# 08_-_Resolver.net
KiCad netlist of a schematic drawn in Altium Designer
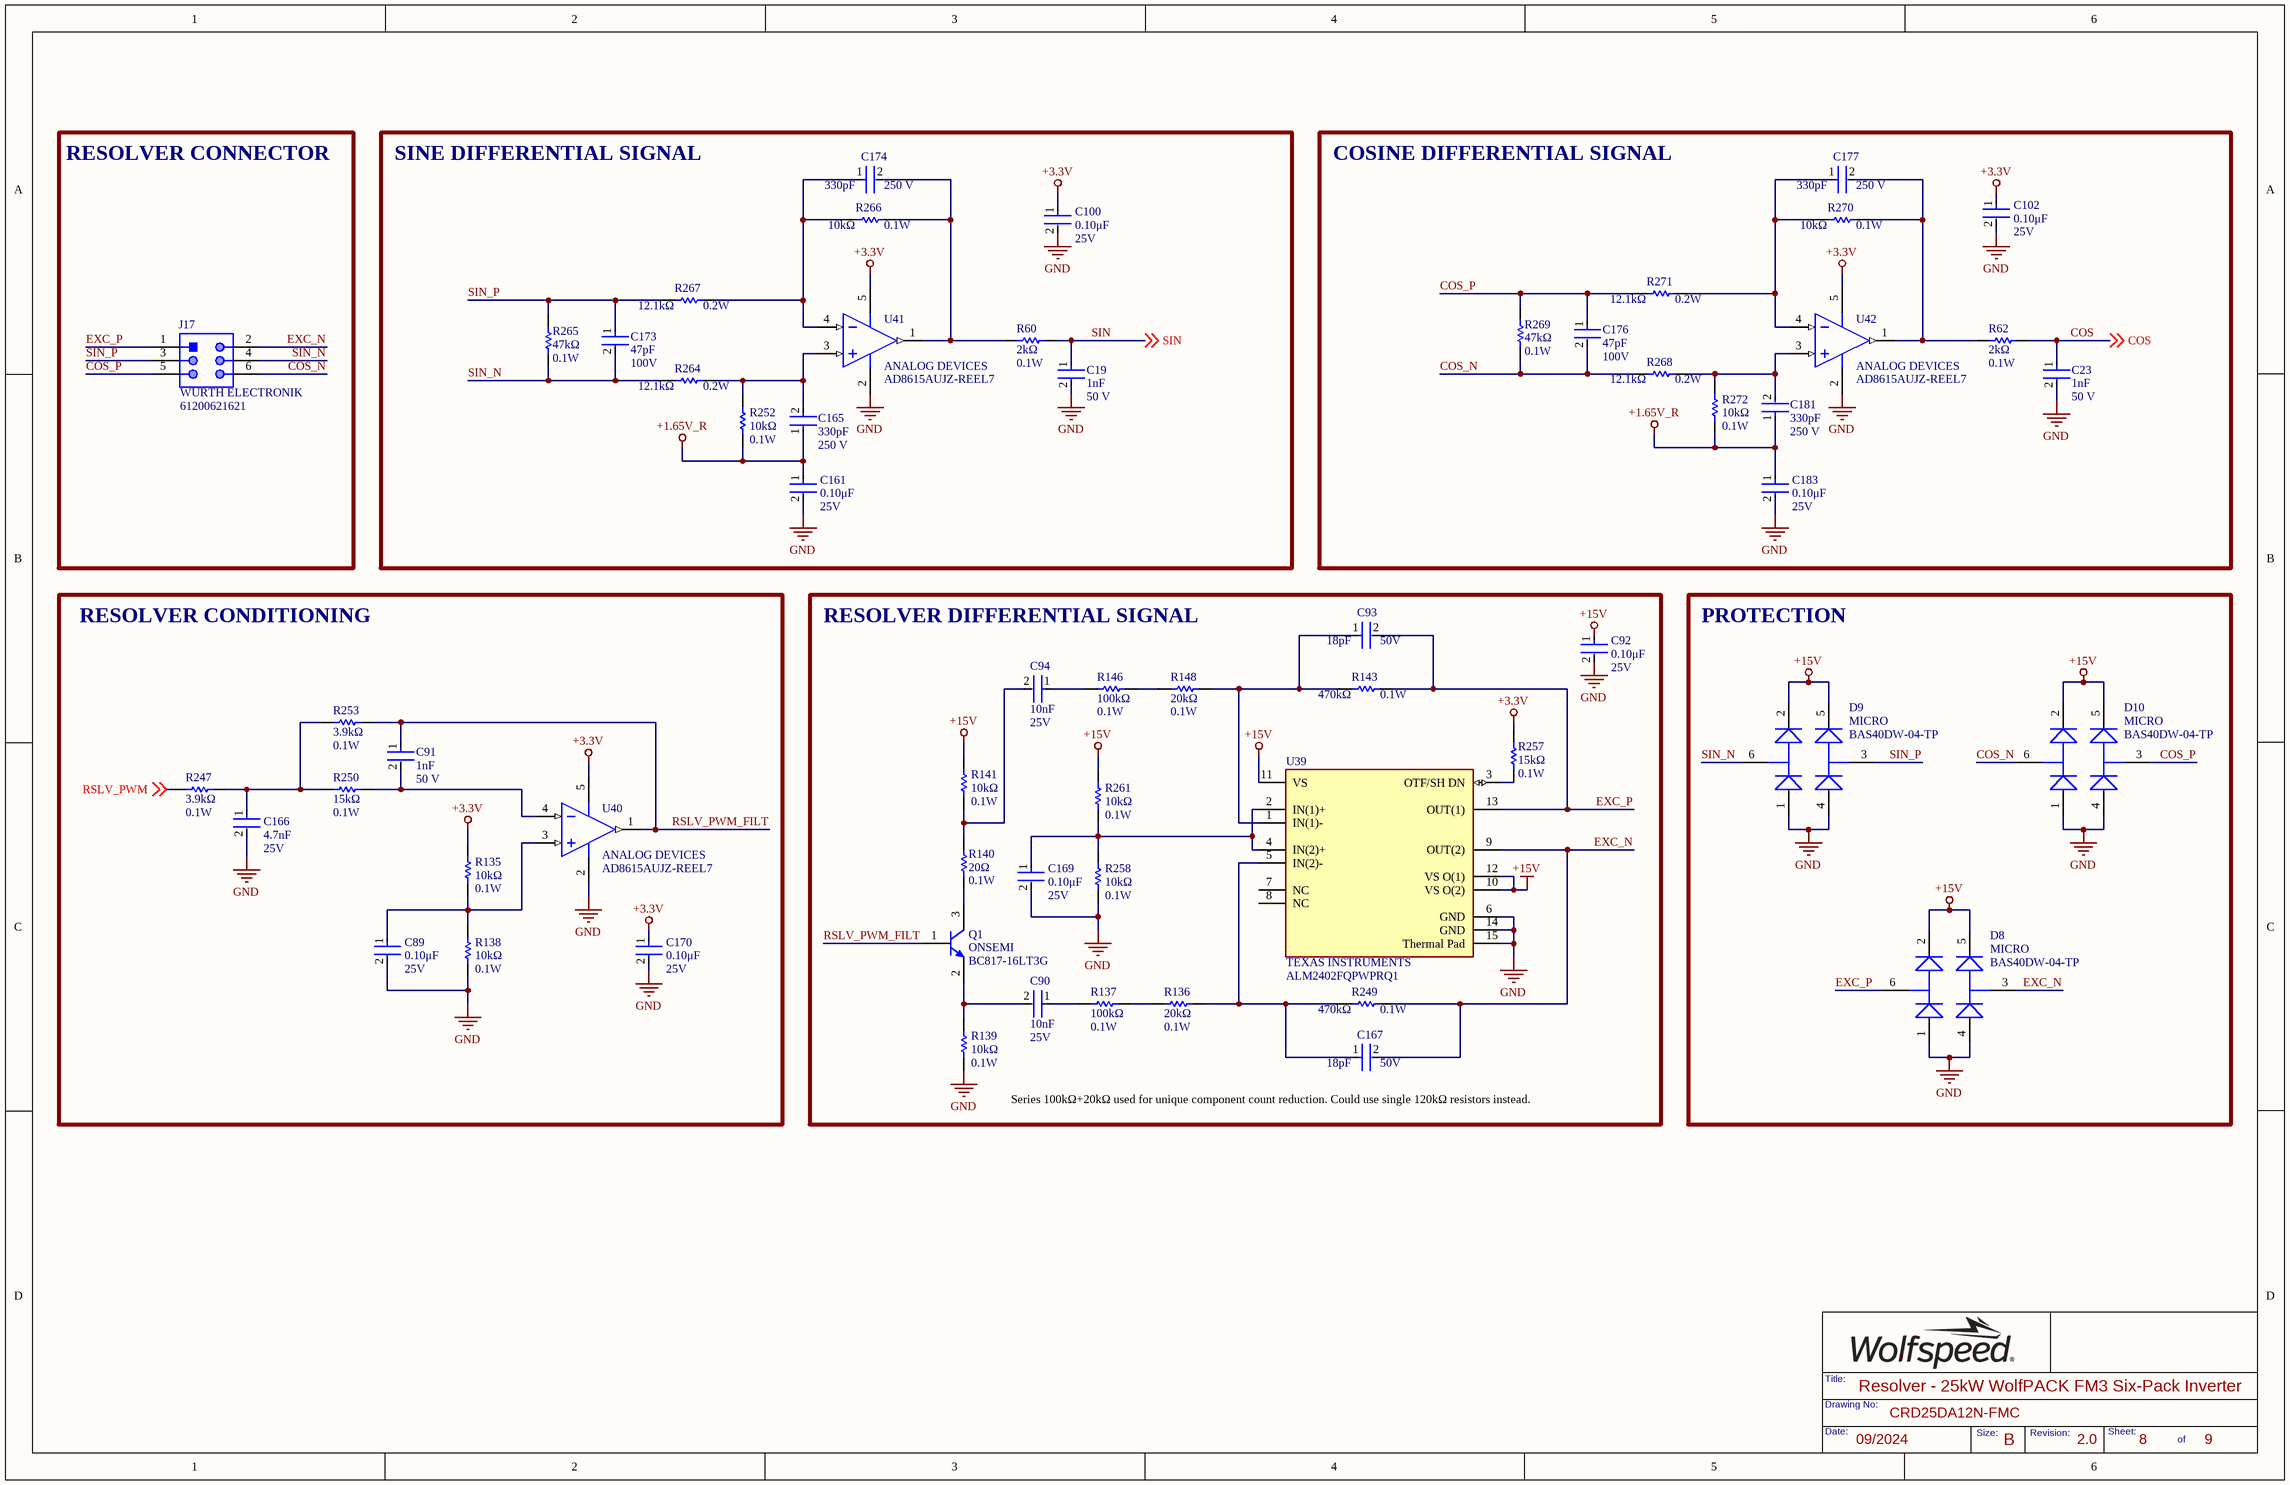
[diagram p0: 08 - Resolver.SchDoc]

(export (version "E")
  (design (tool "Eeschema 10.0.6"))
  (components
    (comp (ref "C19")
      (value "C0603C102K5RACAUTO")
      (footprint "FP-C0603C-CF-IPC_B")
      (description "CAP CER 1000PF 50V X7R 0603")
      (fields
        (field (name "CAPACITANCE") "1nF")
        (field (name "TOLERANCE") "0.1")
        (field (name "VOLTAGE RATING") "50 V")
        (field (name "OCTOPART") "https://octopart.com/c0603c102k5racauto-kemet-18822673")
      )
      (libsource (lib "Altium Content Vault") (part "b4654b650e69147ec39a6b967a45e02"))
    )
    (comp (ref "C23")
      (value "C0603C102K5RACAUTO")
      (footprint "FP-C0603C-CF-IPC_B")
      (description "CAP CER 1000PF 50V X7R 0603")
      (fields
        (field (name "CAPACITANCE") "1nF")
        (field (name "TOLERANCE") "0.1")
        (field (name "VOLTAGE RATING") "50 V")
        (field (name "OCTOPART") "https://octopart.com/c0603c102k5racauto-kemet-18822673")
      )
      (libsource (lib "Altium Content Vault") (part "b4654b650e69147ec39a6b967a45e02"))
    )
    (comp (ref "C89")
      (value "C0603C104K3RACTU")
      (footprint "FP-C0603C-CF-IPC_B")
      (description "CAP CER 0.1UF 25V X7R 0603")
      (fields
        (field (name "VOLTAGE RATING") "25V")
        (field (name "OCTOPART") "https://octopart.com/c0603c104k3ractu-kemet-127541")
        (field (name "MANUFACTURER") "KEMET")
        (field (name "CAPACITANCE") "0.10μF")
      )
      (libsource (lib "Altium Content Vault") (part "b4654b650e69147ec39a6b967a45e02"))
    )
    (comp (ref "C90")
      (value "10nF")
      (footprint "FP-C0603C-CF-IPC_B")
      (description "CAP CER 10000PF 25V X7R 0603")
      (fields
        (field (name "MANUFACTURER") "SAMSUNG")
        (field (name "MANUFACTURER PART NUMBER") "CL10B103KA8WPNC")
        (field (name "VOLTAGE RATING") "25V")
      )
      (libsource (lib "Inverter_25kW") (part "CL10B103KA8WPNC"))
    )
    (comp (ref "C91")
      (value "C0603C102K5RACAUTO")
      (footprint "FP-C0603C-CF-IPC_B")
      (description "CAP CER 1000PF 50V X7R 0603")
      (fields
        (field (name "CAPACITANCE") "1nF")
        (field (name "TOLERANCE") "0.1")
        (field (name "VOLTAGE RATING") "50 V")
        (field (name "OCTOPART") "https://octopart.com/c0603c102k5racauto-kemet-18822673")
      )
      (libsource (lib "Altium Content Vault") (part "b4654b650e69147ec39a6b967a45e02"))
    )
    (comp (ref "C92")
      (value "C0603C104K3RACTU")
      (footprint "FP-C0603C-CF-IPC_B")
      (description "CAP CER 0.1UF 25V X7R 0603")
      (fields
        (field (name "VOLTAGE RATING") "25V")
        (field (name "OCTOPART") "https://octopart.com/c0603c104k3ractu-kemet-127541")
        (field (name "MANUFACTURER") "KEMET")
        (field (name "CAPACITANCE") "0.10μF")
      )
      (libsource (lib "Altium Content Vault") (part "b4654b650e69147ec39a6b967a45e02"))
    )
    (comp (ref "C93")
      (value "06035A180JAT2A")
      (footprint "FP-C0603C-CF-IPC_B")
      (description "CAP CER 18PF 50V C0G/NP0 0603")
      (fields
        (field (name "MANUFACTURER") "KYOCERA AVX")
        (field (name "TOLERANCE") "5%")
        (field (name "CAPACITANCE") "18pF")
        (field (name "VOLTAGE RATING") "50V")
      )
      (libsource (lib "Inverter_25kW") (part "06035A180JAT2A"))
    )
    (comp (ref "C94")
      (value "10nF")
      (footprint "FP-C0603C-CF-IPC_B")
      (description "CAP CER 10000PF 25V X7R 0603")
      (fields
        (field (name "MANUFACTURER") "SAMSUNG")
        (field (name "MANUFACTURER PART NUMBER") "CL10B103KA8WPNC")
        (field (name "VOLTAGE RATING") "25V")
      )
      (libsource (lib "Inverter_25kW") (part "CL10B103KA8WPNC"))
    )
    (comp (ref "C100")
      (value "C0603C104K3RACTU")
      (footprint "FP-C0603C-CF-IPC_B")
      (description "CAP CER 0.1UF 25V X7R 0603")
      (fields
        (field (name "VOLTAGE RATING") "25V")
        (field (name "OCTOPART") "https://octopart.com/c0603c104k3ractu-kemet-127541")
        (field (name "MANUFACTURER") "KEMET")
        (field (name "CAPACITANCE") "0.10μF")
      )
      (libsource (lib "Altium Content Vault") (part "b4654b650e69147ec39a6b967a45e02"))
    )
    (comp (ref "C102")
      (value "C0603C104K3RACTU")
      (footprint "FP-C0603C-CF-IPC_B")
      (description "CAP CER 0.1UF 25V X7R 0603")
      (fields
        (field (name "VOLTAGE RATING") "25V")
        (field (name "OCTOPART") "https://octopart.com/c0603c104k3ractu-kemet-127541")
        (field (name "MANUFACTURER") "KEMET")
        (field (name "CAPACITANCE") "0.10μF")
      )
      (libsource (lib "Altium Content Vault") (part "b4654b650e69147ec39a6b967a45e02"))
    )
    (comp (ref "C161")
      (value "C0603C104K3RACTU")
      (footprint "FP-C0603C-CF-IPC_B")
      (description "CAP CER 0.1UF 25V X7R 0603")
      (fields
        (field (name "VOLTAGE RATING") "25V")
        (field (name "OCTOPART") "https://octopart.com/c0603c104k3ractu-kemet-127541")
        (field (name "MANUFACTURER") "KEMET")
        (field (name "CAPACITANCE") "0.10μF")
      )
      (libsource (lib "Altium Content Vault") (part "b4654b650e69147ec39a6b967a45e02"))
    )
    (comp (ref "C165")
      (value "330pF")
      (footprint "FP-C0603C-CF-IPC_B")
      (description "CAP CER 330PF 250V C0G/NP0 0603")
      (fields
        (field (name "OCTOPART") "https://octopart.com/c0603c331jagac7867-kemet-83501965")
        (field (name "MANUFACTURER PART NUMBER") "C0603C331JAGAC7867")
        (field (name "VOLTAGE RATING") "250 V")
      )
      (libsource (lib "Altium Content Vault") (part "b4654b650e69147ec39a6b967a45e02"))
    )
    (comp (ref "C166")
      (value "C0603C472K3RAC7867")
      (footprint "FP-C0603C-CF-IPC_B")
      (description "CAP CER 4700PF 25V 10% X7R 0603")
      (fields
        (field (name "MANUFACTURER") "KEMET")
        (field (name "MANUFACTURER PART NUMBER") "C0603C472K3RACTU")
        (field (name "VOLTAGE RATING") "25V")
        (field (name "CAPACITANCE") "4.7nF")
      )
      (libsource (lib "Inverter_25kW") (part "C0603C472K3RAC7867"))
    )
    (comp (ref "C167")
      (value "06035A180JAT2A")
      (footprint "FP-C0603C-CF-IPC_B")
      (description "CAP CER 18PF 50V C0G/NP0 0603")
      (fields
        (field (name "MANUFACTURER") "KYOCERA AVX")
        (field (name "TOLERANCE") "5%")
        (field (name "CAPACITANCE") "18pF")
        (field (name "VOLTAGE RATING") "50V")
      )
      (libsource (lib "Inverter_25kW") (part "06035A180JAT2A"))
    )
    (comp (ref "C169")
      (value "C0603C104K3RACTU")
      (footprint "FP-C0603C-CF-IPC_B")
      (description "CAP CER 0.1UF 25V X7R 0603")
      (fields
        (field (name "VOLTAGE RATING") "25V")
        (field (name "OCTOPART") "https://octopart.com/c0603c104k3ractu-kemet-127541")
        (field (name "MANUFACTURER") "KEMET")
        (field (name "CAPACITANCE") "0.10μF")
      )
      (libsource (lib "Altium Content Vault") (part "b4654b650e69147ec39a6b967a45e02"))
    )
    (comp (ref "C170")
      (value "C0603C104K3RACTU")
      (footprint "FP-C0603C-CF-IPC_B")
      (description "CAP CER 0.1UF 25V X7R 0603")
      (fields
        (field (name "VOLTAGE RATING") "25V")
        (field (name "OCTOPART") "https://octopart.com/c0603c104k3ractu-kemet-127541")
        (field (name "MANUFACTURER") "KEMET")
        (field (name "CAPACITANCE") "0.10μF")
      )
      (libsource (lib "Altium Content Vault") (part "b4654b650e69147ec39a6b967a45e02"))
    )
    (comp (ref "C173")
      (value "C0603C470J1GACTU")
      (footprint "FP-C0603C-CF-IPC_B")
      (description "CAP CER 47PF 100V C0G/NP0 0603")
      (fields
        (field (name "MANUFACTURER") "KEMET")
        (field (name "TOLERANCE") "5%")
        (field (name "CAPACITANCE") "47pF")
        (field (name "VOLTAGE RATING (DC)") "100V")
      )
      (libsource (lib "Inverter_25kW") (part "C0603C470J1GACTU"))
    )
    (comp (ref "C174")
      (value "330pF")
      (footprint "FP-C0603C-CF-IPC_B")
      (description "CAP CER 330PF 250V C0G/NP0 0603")
      (fields
        (field (name "OCTOPART") "https://octopart.com/c0603c331jagac7867-kemet-83501965")
        (field (name "MANUFACTURER PART NUMBER") "C0603C331JAGAC7867")
        (field (name "VOLTAGE RATING") "250 V")
      )
      (libsource (lib "Altium Content Vault") (part "b4654b650e69147ec39a6b967a45e02"))
    )
    (comp (ref "C176")
      (value "C0603C470J1GACTU")
      (footprint "FP-C0603C-CF-IPC_B")
      (description "CAP CER 47PF 100V C0G/NP0 0603")
      (fields
        (field (name "MANUFACTURER") "KEMET")
        (field (name "TOLERANCE") "5%")
        (field (name "CAPACITANCE") "47pF")
        (field (name "VOLTAGE RATING (DC)") "100V")
      )
      (libsource (lib "Inverter_25kW") (part "C0603C470J1GACTU"))
    )
    (comp (ref "C177")
      (value "330pF")
      (footprint "FP-C0603C-CF-IPC_B")
      (description "CAP CER 330PF 250V C0G/NP0 0603")
      (fields
        (field (name "OCTOPART") "https://octopart.com/c0603c331jagac7867-kemet-83501965")
        (field (name "MANUFACTURER PART NUMBER") "C0603C331JAGAC7867")
        (field (name "VOLTAGE RATING") "250 V")
      )
      (libsource (lib "Altium Content Vault") (part "b4654b650e69147ec39a6b967a45e02"))
    )
    (comp (ref "C181")
      (value "330pF")
      (footprint "FP-C0603C-CF-IPC_B")
      (description "CAP CER 330PF 250V C0G/NP0 0603")
      (fields
        (field (name "OCTOPART") "https://octopart.com/c0603c331jagac7867-kemet-83501965")
        (field (name "MANUFACTURER PART NUMBER") "C0603C331JAGAC7867")
        (field (name "VOLTAGE RATING") "250 V")
      )
      (libsource (lib "Altium Content Vault") (part "b4654b650e69147ec39a6b967a45e02"))
    )
    (comp (ref "C183")
      (value "C0603C104K3RACTU")
      (footprint "FP-C0603C-CF-IPC_B")
      (description "CAP CER 0.1UF 25V X7R 0603")
      (fields
        (field (name "VOLTAGE RATING") "25V")
        (field (name "OCTOPART") "https://octopart.com/c0603c104k3ractu-kemet-127541")
        (field (name "MANUFACTURER") "KEMET")
        (field (name "CAPACITANCE") "0.10μF")
      )
      (libsource (lib "Altium Content Vault") (part "b4654b650e69147ec39a6b967a45e02"))
    )
    (comp (ref "D8")
      (value "BAS40DW-04-TP")
      (footprint "SOT65P222X120-6N")
      (description "DIODE ARRAY SCHOTTKY 40V SOT363")
      (fields
        (field (name "MANUFACTURER") "MICRO COMMERCIAL")
        (field (name "MANUFACTURER PRINT") "MICRO")
        (field (name "MANUFACTURER PART NUMBER") "BAS40DW-04-TP")
      )
      (libsource (lib "Inverter_25kW") (part "BAS40DW-04-TP"))
    )
    (comp (ref "D9")
      (value "BAS40DW-04-TP")
      (footprint "SOT65P222X120-6N")
      (description "DIODE ARRAY SCHOTTKY 40V SOT363")
      (fields
        (field (name "MANUFACTURER") "MICRO COMMERCIAL")
        (field (name "MANUFACTURER PRINT") "MICRO")
        (field (name "MANUFACTURER PART NUMBER") "BAS40DW-04-TP")
      )
      (libsource (lib "Inverter_25kW") (part "BAS40DW-04-TP"))
    )
    (comp (ref "D10")
      (value "BAS40DW-04-TP")
      (footprint "SOT65P222X120-6N")
      (description "DIODE ARRAY SCHOTTKY 40V SOT363")
      (fields
        (field (name "MANUFACTURER") "MICRO COMMERCIAL")
        (field (name "MANUFACTURER PRINT") "MICRO")
        (field (name "MANUFACTURER PART NUMBER") "BAS40DW-04-TP")
      )
      (libsource (lib "Inverter_25kW") (part "BAS40DW-04-TP"))
    )
    (comp (ref "J17")
      (value "61200621621")
      (footprint "61200621621")
      (description "CONN HEADER VERT 6POS 2.54MM")
      (fields
        (field (name "MANUFACTURER PART NUMBER") "61200621621")
        (field (name "MANUFACTURER") "WURTH ELECTRONIK")
        (field (name "PUBLISHER") "WurthElektronik")
      )
      (libsource (lib "Altium Content Vault") (part "WE-CN-2P-M-R6"))
    )
    (comp (ref "Q1")
      (value "BC817-16LT3G")
      (footprint "ONSC-SOT-23-3-318-08_V")
      (description "TRANS NPN 45V 0.5A SOT23-3")
      (fields (field (name "MANUFACTURER") "ONSEMI") (field (name "MANUFACTURER PART NUMBER") "BC817-16LT3G"))
      (libsource (lib "Altium Content Vault") (part "ONSC-NPN-B1E2C3-3"))
    )
    (comp (ref "R60")
      (value "RT0603DRE072KL")
      (footprint "FP-MCR03-IPC_B")
      (description "RES SMD 2K OHM 0.5% 1/10W 0603")
      (fields
        (field (name "MANUFACTURER") "YAGEO")
        (field (name "TOLERANCE") "0.5%")
        (field (name "RESISTANCE") "2kΩ")
        (field (name "POWER RATING") "0.1W")
      )
      (libsource (lib "Inverter_25kW") (part "RT0603DRE072KL"))
    )
    (comp (ref "R62")
      (value "RT0603DRE072KL")
      (footprint "FP-MCR03-IPC_B")
      (description "RES SMD 2K OHM 0.5% 1/10W 0603")
      (fields
        (field (name "MANUFACTURER") "YAGEO")
        (field (name "TOLERANCE") "0.5%")
        (field (name "RESISTANCE") "2kΩ")
        (field (name "POWER RATING") "0.1W")
      )
      (libsource (lib "Inverter_25kW") (part "RT0603DRE072KL"))
    )
    (comp (ref "R135")
      (value "ERJ3EKF1002V")
      (footprint "FP-MCR03-IPC_B")
      (description "RES SMD 10K OHM 1% 1/10W 0603")
      (fields
        (field (name "MANUFACTURER") "PANASONIC")
        (field (name "MANUFACTURER PART NUMBER") "ERJ-3EKF1002V")
        (field (name "RESISTANCE") "10kΩ")
        (field (name "MAX POWER DISSIPATION") "0.1W")
      )
      (libsource (lib "Inverter_25kW") (part "ERJ3EKF1002V"))
    )
    (comp (ref "R136")
      (value "CRCW060320K0FKTA")
      (footprint "FP-MCR03-IPC_B")
      (description "RES SMD 20K OHM 1% 1/10W 0603")
      (fields
        (field (name "MANUFACTURER") "VISHAY DALE")
        (field (name "TOLERANCE") "1%")
        (field (name "RESISTANCE") "20kΩ")
        (field (name "POWER RATING") "0.1W")
      )
      (libsource (lib "Inverter_25kW") (part "CRCW060320K0FKTA"))
    )
    (comp (ref "R137")
      (value "RC0603FR-07100KL")
      (footprint "FP-MCR03-IPC_B")
      (description "RES 100K OHM 1% 1/10W 0603")
      (fields
        (field (name "MANUFACTURER") "YAGEO")
        (field (name "TOLERANCE") "1%")
        (field (name "RESISTANCE") "100kΩ")
        (field (name "POWER RATING") "0.1W")
      )
      (libsource (lib "Inverter_25kW") (part "RC0603FR-07100KL"))
    )
    (comp (ref "R138")
      (value "ERJ3EKF1002V")
      (footprint "FP-MCR03-IPC_B")
      (description "RES SMD 10K OHM 1% 1/10W 0603")
      (fields
        (field (name "MANUFACTURER") "PANASONIC")
        (field (name "MANUFACTURER PART NUMBER") "ERJ-3EKF1002V")
        (field (name "RESISTANCE") "10kΩ")
        (field (name "MAX POWER DISSIPATION") "0.1W")
      )
      (libsource (lib "Inverter_25kW") (part "ERJ3EKF1002V"))
    )
    (comp (ref "R139")
      (value "ERJ3EKF1002V")
      (footprint "FP-MCR03-IPC_B")
      (description "RES SMD 10K OHM 1% 1/10W 0603")
      (fields
        (field (name "MANUFACTURER") "PANASONIC")
        (field (name "MANUFACTURER PART NUMBER") "ERJ-3EKF1002V")
        (field (name "RESISTANCE") "10kΩ")
        (field (name "MAX POWER DISSIPATION") "0.1W")
      )
      (libsource (lib "Inverter_25kW") (part "ERJ3EKF1002V"))
    )
    (comp (ref "R140")
      (value "RC0603JR-0720RL")
      (footprint "FP-MCR03-IPC_B")
      (description "RES 20 OHM 5% 1/10W 0603")
      (fields
        (field (name "MANUFACTURER") "YAGEO")
        (field (name "TOLERANCE") "5%")
        (field (name "RESISTANCE") "20Ω")
        (field (name "POWER RATING") "0.1W")
      )
      (libsource (lib "Inverter_25kW") (part "RC0603JR-0720RL"))
    )
    (comp (ref "R141")
      (value "ERJ3EKF1002V")
      (footprint "FP-MCR03-IPC_B")
      (description "RES SMD 10K OHM 1% 1/10W 0603")
      (fields
        (field (name "MANUFACTURER") "PANASONIC")
        (field (name "MANUFACTURER PART NUMBER") "ERJ-3EKF1002V")
        (field (name "RESISTANCE") "10kΩ")
        (field (name "MAX POWER DISSIPATION") "0.1W")
      )
      (libsource (lib "Inverter_25kW") (part "ERJ3EKF1002V"))
    )
    (comp (ref "R143")
      (value "RC0603FR-07470KL")
      (footprint "FP-MCR03-IPC_B")
      (description "RES 470K OHM 1% 1/10W 0603")
      (fields
        (field (name "MANUFACTURER") "YAGEO")
        (field (name "TOLERANCE") "1%")
        (field (name "RESISTANCE") "470kΩ")
        (field (name "POWER RATING") "0.1W")
      )
      (libsource (lib "Inverter_25kW") (part "RC0603FR-07470KL"))
    )
    (comp (ref "R146")
      (value "RC0603FR-07100KL")
      (footprint "FP-MCR03-IPC_B")
      (description "RES 100K OHM 1% 1/10W 0603")
      (fields
        (field (name "MANUFACTURER") "YAGEO")
        (field (name "TOLERANCE") "1%")
        (field (name "RESISTANCE") "100kΩ")
        (field (name "POWER RATING") "0.1W")
      )
      (libsource (lib "Inverter_25kW") (part "RC0603FR-07100KL"))
    )
    (comp (ref "R148")
      (value "CRCW060320K0FKTA")
      (footprint "FP-MCR03-IPC_B")
      (description "RES SMD 20K OHM 1% 1/10W 0603")
      (fields
        (field (name "MANUFACTURER") "VISHAY DALE")
        (field (name "TOLERANCE") "1%")
        (field (name "RESISTANCE") "20kΩ")
        (field (name "POWER RATING") "0.1W")
      )
      (libsource (lib "Inverter_25kW") (part "CRCW060320K0FKTA"))
    )
    (comp (ref "R247")
      (value "ERJ3EKF3901V")
      (footprint "FP-MCR03-IPC_B")
      (description "RES SMD 3.9K OHM 1% 1/10W 0603")
      (fields
        (field (name "MANUFACTURER") "PANASONIC")
        (field (name "MANUFACTURER PART NUMBER") "ERJ-3EKF3901V")
        (field (name "RESISTANCE") "3.9kΩ")
        (field (name "POWER RATING") "0.1W")
      )
      (libsource (lib "Inverter_25kW") (part "ERJ3EKF3901V"))
    )
    (comp (ref "R249")
      (value "RC0603FR-07470KL")
      (footprint "FP-MCR03-IPC_B")
      (description "RES 470K OHM 1% 1/10W 0603")
      (fields
        (field (name "MANUFACTURER") "YAGEO")
        (field (name "TOLERANCE") "1%")
        (field (name "RESISTANCE") "470kΩ")
        (field (name "POWER RATING") "0.1W")
      )
      (libsource (lib "Inverter_25kW") (part "RC0603FR-07470KL"))
    )
    (comp (ref "R250")
      (value "ERA-3AED153V")
      (footprint "FP-MCR03-IPC_B")
      (description "RES SMD 15K OHM 0.5% 1/10W 0603")
      (fields
        (field (name "MANUFACTURER") "PANASONIC")
        (field (name "TOLERANCE") "0.5%")
        (field (name "RESISTANCE") "15kΩ")
        (field (name "POWER RATING") "0.1W")
      )
      (libsource (lib "Inverter_25kW") (part "ERA-3AED153V"))
    )
    (comp (ref "R252")
      (value "ERJ3EKF1002V")
      (footprint "FP-MCR03-IPC_B")
      (description "RES SMD 10K OHM 1% 1/10W 0603")
      (fields
        (field (name "MANUFACTURER") "PANASONIC")
        (field (name "MANUFACTURER PART NUMBER") "ERJ-3EKF1002V")
        (field (name "RESISTANCE") "10kΩ")
        (field (name "MAX POWER DISSIPATION") "0.1W")
      )
      (libsource (lib "Inverter_25kW") (part "ERJ3EKF1002V"))
    )
    (comp (ref "R253")
      (value "ERJ3EKF3901V")
      (footprint "FP-MCR03-IPC_B")
      (description "RES SMD 3.9K OHM 1% 1/10W 0603")
      (fields
        (field (name "MANUFACTURER") "PANASONIC")
        (field (name "MANUFACTURER PART NUMBER") "ERJ-3EKF3901V")
        (field (name "RESISTANCE") "3.9kΩ")
        (field (name "POWER RATING") "0.1W")
      )
      (libsource (lib "Inverter_25kW") (part "ERJ3EKF3901V"))
    )
    (comp (ref "R257")
      (value "ERA-3AED153V")
      (footprint "FP-MCR03-IPC_B")
      (description "RES SMD 15K OHM 0.5% 1/10W 0603")
      (fields
        (field (name "MANUFACTURER") "PANASONIC")
        (field (name "TOLERANCE") "0.5%")
        (field (name "RESISTANCE") "15kΩ")
        (field (name "POWER RATING") "0.1W")
      )
      (libsource (lib "Inverter_25kW") (part "ERA-3AED153V"))
    )
    (comp (ref "R258")
      (value "ERJ3EKF1002V")
      (footprint "FP-MCR03-IPC_B")
      (description "RES SMD 10K OHM 1% 1/10W 0603")
      (fields
        (field (name "MANUFACTURER") "PANASONIC")
        (field (name "MANUFACTURER PART NUMBER") "ERJ-3EKF1002V")
        (field (name "RESISTANCE") "10kΩ")
        (field (name "MAX POWER DISSIPATION") "0.1W")
      )
      (libsource (lib "Inverter_25kW") (part "ERJ3EKF1002V"))
    )
    (comp (ref "R261")
      (value "ERJ3EKF1002V")
      (footprint "FP-MCR03-IPC_B")
      (description "RES SMD 10K OHM 1% 1/10W 0603")
      (fields
        (field (name "MANUFACTURER") "PANASONIC")
        (field (name "MANUFACTURER PART NUMBER") "ERJ-3EKF1002V")
        (field (name "RESISTANCE") "10kΩ")
        (field (name "MAX POWER DISSIPATION") "0.1W")
      )
      (libsource (lib "Inverter_25kW") (part "ERJ3EKF1002V"))
    )
    (comp (ref "R264")
      (value "ERJ-PB3B1212V")
      (footprint "FP-MCR03-IPC_B")
      (description "RES SMD 12.1K OHM 0.1% 1/5W 0603")
      (fields
        (field (name "MANUFACTURER") "PANASONIC")
        (field (name "TOLERANCE") "0.1%")
        (field (name "RESISTANCE") "12.1kΩ")
        (field (name "MAX POWER DISSIPATION") "0.2W")
      )
      (libsource (lib "Inverter_25kW") (part "ERJ-PB3B1212V"))
    )
    (comp (ref "R265")
      (value "RC0603FR-0747KL")
      (footprint "FP-MCR03-IPC_B")
      (description "RES 47K OHM 1% 1/10W 0603")
      (fields
        (field (name "MANUFACTURER") "YAGEO")
        (field (name "TOLERANCE") "1%")
        (field (name "RESISTANCE") "47kΩ")
        (field (name "POWER RATING") "0.1W")
      )
      (libsource (lib "Inverter_25kW") (part "RC0603FR-0747KL"))
    )
    (comp (ref "R266")
      (value "ERJ3EKF1002V")
      (footprint "FP-MCR03-IPC_B")
      (description "RES SMD 10K OHM 1% 1/10W 0603")
      (fields
        (field (name "MANUFACTURER") "PANASONIC")
        (field (name "MANUFACTURER PART NUMBER") "ERJ-3EKF1002V")
        (field (name "RESISTANCE") "10kΩ")
        (field (name "MAX POWER DISSIPATION") "0.1W")
      )
      (libsource (lib "Inverter_25kW") (part "ERJ3EKF1002V"))
    )
    (comp (ref "R267")
      (value "ERJ-PB3B1212V")
      (footprint "FP-MCR03-IPC_B")
      (description "RES SMD 12.1K OHM 0.1% 1/5W 0603")
      (fields
        (field (name "MANUFACTURER") "PANASONIC")
        (field (name "TOLERANCE") "0.1%")
        (field (name "RESISTANCE") "12.1kΩ")
        (field (name "MAX POWER DISSIPATION") "0.2W")
      )
      (libsource (lib "Inverter_25kW") (part "ERJ-PB3B1212V"))
    )
    (comp (ref "R268")
      (value "ERJ-PB3B1212V")
      (footprint "FP-MCR03-IPC_B")
      (description "RES SMD 12.1K OHM 0.1% 1/5W 0603")
      (fields
        (field (name "MANUFACTURER") "PANASONIC")
        (field (name "TOLERANCE") "0.1%")
        (field (name "RESISTANCE") "12.1kΩ")
        (field (name "MAX POWER DISSIPATION") "0.2W")
      )
      (libsource (lib "Inverter_25kW") (part "ERJ-PB3B1212V"))
    )
    (comp (ref "R269")
      (value "RC0603FR-0747KL")
      (footprint "FP-MCR03-IPC_B")
      (description "RES 47K OHM 1% 1/10W 0603")
      (fields
        (field (name "MANUFACTURER") "YAGEO")
        (field (name "TOLERANCE") "1%")
        (field (name "RESISTANCE") "47kΩ")
        (field (name "POWER RATING") "0.1W")
      )
      (libsource (lib "Inverter_25kW") (part "RC0603FR-0747KL"))
    )
    (comp (ref "R270")
      (value "ERJ3EKF1002V")
      (footprint "FP-MCR03-IPC_B")
      (description "RES SMD 10K OHM 1% 1/10W 0603")
      (fields
        (field (name "MANUFACTURER") "PANASONIC")
        (field (name "MANUFACTURER PART NUMBER") "ERJ-3EKF1002V")
        (field (name "RESISTANCE") "10kΩ")
        (field (name "MAX POWER DISSIPATION") "0.1W")
      )
      (libsource (lib "Inverter_25kW") (part "ERJ3EKF1002V"))
    )
    (comp (ref "R271")
      (value "ERJ-PB3B1212V")
      (footprint "FP-MCR03-IPC_B")
      (description "RES SMD 12.1K OHM 0.1% 1/5W 0603")
      (fields
        (field (name "MANUFACTURER") "PANASONIC")
        (field (name "TOLERANCE") "0.1%")
        (field (name "RESISTANCE") "12.1kΩ")
        (field (name "MAX POWER DISSIPATION") "0.2W")
      )
      (libsource (lib "Inverter_25kW") (part "ERJ-PB3B1212V"))
    )
    (comp (ref "R272")
      (value "ERJ3EKF1002V")
      (footprint "FP-MCR03-IPC_B")
      (description "RES SMD 10K OHM 1% 1/10W 0603")
      (fields
        (field (name "MANUFACTURER") "PANASONIC")
        (field (name "MANUFACTURER PART NUMBER") "ERJ-3EKF1002V")
        (field (name "RESISTANCE") "10kΩ")
        (field (name "MAX POWER DISSIPATION") "0.1W")
      )
      (libsource (lib "Inverter_25kW") (part "ERJ3EKF1002V"))
    )
    (comp (ref "U39")
      (value "ALM2402FQPWPRQ1")
      (footprint "FP-PWP0014H-MFG")
      (description "IC POWER 2 CIRCUIT 14HTSSOP")
      (fields
        (field (name "MANUFACTURER PART NUMBER") "ALM2402FQPWPRQ1")
        (field (name "MANUFACTURER") "TEXAS INSTRUMENTS")
      )
      (libsource (lib "CRD25DA12N-FMC") (part "CMP-04895-000282-1"))
    )
    (comp (ref "U40")
      (value "AD8615AUJZ-REEL7")
      (footprint "ADI-UJ-5_M")
      (description "IC OPAMP GP 1 CIRCUIT TSOT23-5")
      (fields
        (field (name "MANUFACTURER") "ANALOG DEVICES")
        (field (name "GENERIC PART NUMBER") "AD8615")
        (field (name "MANUFACTURER PART NUMBER") "AD8615AUJZ-REEL7")
      )
      (libsource (lib "Altium Content Vault") (part "ADI-ADxxxx-X-5"))
    )
    (comp (ref "U41")
      (value "AD8615AUJZ-REEL7")
      (footprint "ADI-UJ-5_M")
      (description "IC OPAMP GP 1 CIRCUIT TSOT23-5")
      (fields
        (field (name "MANUFACTURER") "ANALOG DEVICES")
        (field (name "GENERIC PART NUMBER") "AD8615")
        (field (name "MANUFACTURER PART NUMBER") "AD8615AUJZ-REEL7")
      )
      (libsource (lib "Altium Content Vault") (part "ADI-ADxxxx-X-5"))
    )
    (comp (ref "U42")
      (value "AD8615AUJZ-REEL7")
      (footprint "ADI-UJ-5_M")
      (description "IC OPAMP GP 1 CIRCUIT TSOT23-5")
      (fields
        (field (name "MANUFACTURER") "ANALOG DEVICES")
        (field (name "GENERIC PART NUMBER") "AD8615")
        (field (name "MANUFACTURER PART NUMBER") "AD8615AUJZ-REEL7")
      )
      (libsource (lib "Altium Content Vault") (part "ADI-ADxxxx-X-5"))
    )
  )
  (nets
    (net (code "1") (name "+1.65V_R") (class "Default")
      (node (ref "C161") (pin "1") (pinfunction "1_1") (pintype "passive"))
      (node (ref "C165") (pin "1") (pinfunction "1_1") (pintype "passive"))
      (node (ref "C181") (pin "1") (pinfunction "1_1") (pintype "passive"))
      (node (ref "C183") (pin "1") (pinfunction "1_1") (pintype "passive"))
      (node (ref "R252") (pin "1") (pinfunction "1_1") (pintype "passive"))
      (node (ref "R272") (pin "1") (pinfunction "1_1") (pintype "passive"))
    )
    (net (code "2") (name "+3.3V") (class "Default")
      (node (ref "C100") (pin "1") (pinfunction "1_1") (pintype "passive"))
      (node (ref "C102") (pin "1") (pinfunction "1_1") (pintype "passive"))
      (node (ref "C170") (pin "1") (pinfunction "1_1") (pintype "passive"))
      (node (ref "R135") (pin "2") (pinfunction "2_2") (pintype "passive"))
      (node (ref "R257") (pin "2") (pinfunction "2_2") (pintype "passive"))
      (node (ref "U40") (pin "5") (pinfunction "+V_5") (pintype "power_in"))
      (node (ref "U41") (pin "5") (pinfunction "+V_5") (pintype "power_in"))
      (node (ref "U42") (pin "5") (pinfunction "+V_5") (pintype "power_in"))
    )
    (net (code "3") (name "+15V") (class "Default")
      (node (ref "C92") (pin "1") (pinfunction "1_1") (pintype "passive"))
      (node (ref "D10") (pin "2") (pinfunction "C1_2") (pintype "passive"))
      (node (ref "D10") (pin "5") (pinfunction "C2_5") (pintype "passive"))
      (node (ref "D8") (pin "2") (pinfunction "C1_2") (pintype "passive"))
      (node (ref "D8") (pin "5") (pinfunction "C2_5") (pintype "passive"))
      (node (ref "D9") (pin "2") (pinfunction "C1_2") (pintype "passive"))
      (node (ref "D9") (pin "5") (pinfunction "C2_5") (pintype "passive"))
      (node (ref "R141") (pin "2") (pinfunction "2_2") (pintype "passive"))
      (node (ref "R261") (pin "2") (pinfunction "2_2") (pintype "passive"))
      (node (ref "U39") (pin "10") (pinfunction "VS_O(2)_10") (pintype "power_in"))
      (node (ref "U39") (pin "11") (pinfunction "VS_11") (pintype "power_in"))
      (node (ref "U39") (pin "12") (pinfunction "VS_O(1)_12") (pintype "power_in"))
    )
    (net (code "4") (name "/COS_N") (class "Default")
      (node (ref "C176") (pin "2") (pinfunction "2_2") (pintype "passive"))
      (node (ref "D10") (pin "6") (pinfunction "AC1_6") (pintype "passive"))
      (node (ref "J17") (pin "6") (pinfunction "6_6") (pintype "passive"))
      (node (ref "R268") (pin "1") (pinfunction "1_1") (pintype "passive"))
      (node (ref "R269") (pin "1") (pinfunction "1_1") (pintype "passive"))
    )
    (net (code "5") (name "/COS_P") (class "Default")
      (node (ref "C176") (pin "1") (pinfunction "1_1") (pintype "passive"))
      (node (ref "D10") (pin "3") (pinfunction "AC2_3") (pintype "passive"))
      (node (ref "J17") (pin "5") (pinfunction "5_5") (pintype "passive"))
      (node (ref "R269") (pin "2") (pinfunction "2_2") (pintype "passive"))
      (node (ref "R271") (pin "1") (pinfunction "1_1") (pintype "passive"))
    )
    (net (code "6") (name "/EXC_N") (class "Default")
      (node (ref "C167") (pin "2") (pinfunction "2_2") (pintype "passive"))
      (node (ref "D8") (pin "3") (pinfunction "AC2_3") (pintype "passive"))
      (node (ref "J17") (pin "2") (pinfunction "2_2") (pintype "passive"))
      (node (ref "R249") (pin "2") (pinfunction "2_2") (pintype "passive"))
      (node (ref "U39") (pin "9") (pinfunction "OUT(2)_9") (pintype "passive"))
    )
    (net (code "7") (name "/EXC_P") (class "Default")
      (node (ref "C93") (pin "2") (pinfunction "2_2") (pintype "passive"))
      (node (ref "D8") (pin "6") (pinfunction "AC1_6") (pintype "passive"))
      (node (ref "J17") (pin "1") (pinfunction "1_1") (pintype "passive"))
      (node (ref "R143") (pin "2") (pinfunction "2_2") (pintype "passive"))
      (node (ref "U39") (pin "13") (pinfunction "OUT(1)_13") (pintype "passive"))
    )
    (net (code "8") (name "/RSLV_PWM_FILT") (class "Default")
      (node (ref "C91") (pin "1") (pinfunction "1_1") (pintype "passive"))
      (node (ref "Q1") (pin "1") (pinfunction "B_1") (pintype "passive"))
      (node (ref "R253") (pin "2") (pinfunction "2_2") (pintype "passive"))
      (node (ref "U40") (pin "1") (pinfunction "OUT_1") (pintype "output"))
    )
    (net (code "9") (name "/SIN_N") (class "Default")
      (node (ref "C173") (pin "2") (pinfunction "2_2") (pintype "passive"))
      (node (ref "D9") (pin "6") (pinfunction "AC1_6") (pintype "passive"))
      (node (ref "J17") (pin "4") (pinfunction "4_4") (pintype "passive"))
      (node (ref "R264") (pin "1") (pinfunction "1_1") (pintype "passive"))
      (node (ref "R265") (pin "1") (pinfunction "1_1") (pintype "passive"))
    )
    (net (code "10") (name "/SIN_P") (class "Default")
      (node (ref "C173") (pin "1") (pinfunction "1_1") (pintype "passive"))
      (node (ref "D9") (pin "3") (pinfunction "AC2_3") (pintype "passive"))
      (node (ref "J17") (pin "3") (pinfunction "3_3") (pintype "passive"))
      (node (ref "R265") (pin "2") (pinfunction "2_2") (pintype "passive"))
      (node (ref "R267") (pin "1") (pinfunction "1_1") (pintype "passive"))
    )
    (net (code "11") (name "COS") (class "Default")
      (node (ref "C23") (pin "1") (pinfunction "1_1") (pintype "passive"))
      (node (ref "R62") (pin "2") (pinfunction "2_2") (pintype "passive"))
    )
    (net (code "12") (name "GND") (class "Default")
      (node (ref "C100") (pin "2") (pinfunction "2_2") (pintype "passive"))
      (node (ref "C102") (pin "2") (pinfunction "2_2") (pintype "passive"))
      (node (ref "C161") (pin "2") (pinfunction "2_2") (pintype "passive"))
      (node (ref "C166") (pin "2") (pinfunction "2_2") (pintype "passive"))
      (node (ref "C169") (pin "2") (pinfunction "2_2") (pintype "passive"))
      (node (ref "C170") (pin "2") (pinfunction "2_2") (pintype "passive"))
      (node (ref "C183") (pin "2") (pinfunction "2_2") (pintype "passive"))
      (node (ref "C19") (pin "2") (pinfunction "2_2") (pintype "passive"))
      (node (ref "C23") (pin "2") (pinfunction "2_2") (pintype "passive"))
      (node (ref "C89") (pin "2") (pinfunction "2_2") (pintype "passive"))
      (node (ref "C92") (pin "2") (pinfunction "2_2") (pintype "passive"))
      (node (ref "D10") (pin "1") (pinfunction "A1_1") (pintype "passive"))
      (node (ref "D10") (pin "4") (pinfunction "A2_4") (pintype "passive"))
      (node (ref "D8") (pin "1") (pinfunction "A1_1") (pintype "passive"))
      (node (ref "D8") (pin "4") (pinfunction "A2_4") (pintype "passive"))
      (node (ref "D9") (pin "1") (pinfunction "A1_1") (pintype "passive"))
      (node (ref "D9") (pin "4") (pinfunction "A2_4") (pintype "passive"))
      (node (ref "R138") (pin "1") (pinfunction "1_1") (pintype "passive"))
      (node (ref "R139") (pin "1") (pinfunction "1_1") (pintype "passive"))
      (node (ref "R258") (pin "1") (pinfunction "1_1") (pintype "passive"))
      (node (ref "U39") (pin "14") (pinfunction "GND_14") (pintype "power_in"))
      (node (ref "U39") (pin "15") (pinfunction "Thermal_Pad_15") (pintype "power_in"))
      (node (ref "U39") (pin "6") (pinfunction "GND_6") (pintype "power_in"))
      (node (ref "U40") (pin "2") (pinfunction "-V_2") (pintype "power_in"))
      (node (ref "U41") (pin "2") (pinfunction "-V_2") (pintype "power_in"))
      (node (ref "U42") (pin "2") (pinfunction "-V_2") (pintype "power_in"))
    )
    (net (code "13") (name "Net-(C90-Pad1)") (class "Default")
      (node (ref "C90") (pin "1") (pinfunction "1_1") (pintype "passive"))
      (node (ref "R137") (pin "2") (pinfunction "2_2") (pintype "passive"))
    )
    (net (code "14") (name "Net-(C94-Pad1)") (class "Default")
      (node (ref "C94") (pin "1") (pinfunction "1_1") (pintype "passive"))
      (node (ref "R146") (pin "2") (pinfunction "2_2") (pintype "passive"))
    )
    (net (code "15") (name "Net-(C94-Pad2)") (class "Default")
      (node (ref "C94") (pin "2") (pinfunction "2_2") (pintype "passive"))
      (node (ref "R140") (pin "2") (pinfunction "2_2") (pintype "passive"))
      (node (ref "R141") (pin "1") (pinfunction "1_1") (pintype "passive"))
    )
    (net (code "16") (name "Net-(C166-Pad1)") (class "Default")
      (node (ref "C166") (pin "1") (pinfunction "1_1") (pintype "passive"))
      (node (ref "R247") (pin "2") (pinfunction "2_2") (pintype "passive"))
      (node (ref "R250") (pin "2") (pinfunction "2_2") (pintype "passive"))
      (node (ref "R253") (pin "1") (pinfunction "1_1") (pintype "passive"))
    )
    (net (code "17") (name "Net-(Q1-C)") (class "Default")
      (node (ref "Q1") (pin "3") (pinfunction "C_3") (pintype "passive"))
      (node (ref "R140") (pin "1") (pinfunction "1_1") (pintype "passive"))
    )
    (net (code "18") (name "Net-(Q1-E)") (class "Default")
      (node (ref "C90") (pin "2") (pinfunction "2_2") (pintype "passive"))
      (node (ref "Q1") (pin "2") (pinfunction "E_2") (pintype "passive"))
      (node (ref "R139") (pin "2") (pinfunction "2_2") (pintype "passive"))
    )
    (net (code "19") (name "Net-(R136-Pad2)") (class "Default")
      (node (ref "R136") (pin "2") (pinfunction "2_2") (pintype "passive"))
      (node (ref "R137") (pin "1") (pinfunction "1_1") (pintype "passive"))
    )
    (net (code "20") (name "Net-(R146-Pad1)") (class "Default")
      (node (ref "R146") (pin "1") (pinfunction "1_1") (pintype "passive"))
      (node (ref "R148") (pin "2") (pinfunction "2_2") (pintype "passive"))
    )
    (net (code "21") (name "Net-(U39-IN(1)+)") (class "Default")
      (node (ref "C169") (pin "1") (pinfunction "1_1") (pintype "passive"))
      (node (ref "R258") (pin "2") (pinfunction "2_2") (pintype "passive"))
      (node (ref "R261") (pin "1") (pinfunction "1_1") (pintype "passive"))
      (node (ref "U39") (pin "2") (pinfunction "IN(1)+_2") (pintype "tri_state"))
      (node (ref "U39") (pin "4") (pinfunction "IN(2)+_4") (pintype "tri_state"))
    )
    (net (code "22") (name "Net-(U39-IN(1)-)") (class "Default")
      (node (ref "C93") (pin "1") (pinfunction "1_1") (pintype "passive"))
      (node (ref "R143") (pin "1") (pinfunction "1_1") (pintype "passive"))
      (node (ref "R148") (pin "1") (pinfunction "1_1") (pintype "passive"))
      (node (ref "U39") (pin "1") (pinfunction "IN(1)-_1") (pintype "tri_state"))
    )
    (net (code "23") (name "Net-(U39-IN(2)-)") (class "Default")
      (node (ref "C167") (pin "1") (pinfunction "1_1") (pintype "passive"))
      (node (ref "R136") (pin "1") (pinfunction "1_1") (pintype "passive"))
      (node (ref "R249") (pin "1") (pinfunction "1_1") (pintype "passive"))
      (node (ref "U39") (pin "5") (pinfunction "IN(2)-_5") (pintype "tri_state"))
    )
    (net (code "24") (name "Net-(U39-OTF{slash}SH_DN)") (class "Default")
      (node (ref "R257") (pin "1") (pinfunction "1_1") (pintype "passive"))
      (node (ref "U39") (pin "3") (pinfunction "OTF/SH_DN_3") (pintype "bidirectional"))
    )
    (net (code "25") (name "Net-(U40-+IN)") (class "Default")
      (node (ref "C89") (pin "1") (pinfunction "1_1") (pintype "passive"))
      (node (ref "R135") (pin "1") (pinfunction "1_1") (pintype "passive"))
      (node (ref "R138") (pin "2") (pinfunction "2_2") (pintype "passive"))
      (node (ref "U40") (pin "3") (pinfunction "+IN_3") (pintype "input"))
    )
    (net (code "26") (name "Net-(U40--IN)") (class "Default")
      (node (ref "C91") (pin "2") (pinfunction "2_2") (pintype "passive"))
      (node (ref "R250") (pin "1") (pinfunction "1_1") (pintype "passive"))
      (node (ref "U40") (pin "4") (pinfunction "-IN_4") (pintype "input"))
    )
    (net (code "27") (name "Net-(U41-+IN)") (class "Default")
      (node (ref "C165") (pin "2") (pinfunction "2_2") (pintype "passive"))
      (node (ref "R252") (pin "2") (pinfunction "2_2") (pintype "passive"))
      (node (ref "R264") (pin "2") (pinfunction "2_2") (pintype "passive"))
      (node (ref "U41") (pin "3") (pinfunction "+IN_3") (pintype "input"))
    )
    (net (code "28") (name "Net-(U41--IN)") (class "Default")
      (node (ref "C174") (pin "1") (pinfunction "1_1") (pintype "passive"))
      (node (ref "R266") (pin "2") (pinfunction "2_2") (pintype "passive"))
      (node (ref "R267") (pin "2") (pinfunction "2_2") (pintype "passive"))
      (node (ref "U41") (pin "4") (pinfunction "-IN_4") (pintype "input"))
    )
    (net (code "29") (name "Net-(U41-OUT)") (class "Default")
      (node (ref "C174") (pin "2") (pinfunction "2_2") (pintype "passive"))
      (node (ref "R266") (pin "1") (pinfunction "1_1") (pintype "passive"))
      (node (ref "R60") (pin "1") (pinfunction "1_1") (pintype "passive"))
      (node (ref "U41") (pin "1") (pinfunction "OUT_1") (pintype "output"))
    )
    (net (code "30") (name "Net-(U42-+IN)") (class "Default")
      (node (ref "C181") (pin "2") (pinfunction "2_2") (pintype "passive"))
      (node (ref "R268") (pin "2") (pinfunction "2_2") (pintype "passive"))
      (node (ref "R272") (pin "2") (pinfunction "2_2") (pintype "passive"))
      (node (ref "U42") (pin "3") (pinfunction "+IN_3") (pintype "input"))
    )
    (net (code "31") (name "Net-(U42--IN)") (class "Default")
      (node (ref "C177") (pin "1") (pinfunction "1_1") (pintype "passive"))
      (node (ref "R270") (pin "2") (pinfunction "2_2") (pintype "passive"))
      (node (ref "R271") (pin "2") (pinfunction "2_2") (pintype "passive"))
      (node (ref "U42") (pin "4") (pinfunction "-IN_4") (pintype "input"))
    )
    (net (code "32") (name "Net-(U42-OUT)") (class "Default")
      (node (ref "C177") (pin "2") (pinfunction "2_2") (pintype "passive"))
      (node (ref "R270") (pin "1") (pinfunction "1_1") (pintype "passive"))
      (node (ref "R62") (pin "1") (pinfunction "1_1") (pintype "passive"))
      (node (ref "U42") (pin "1") (pinfunction "OUT_1") (pintype "output"))
    )
    (net (code "33") (name "RSLV_PWM") (class "Default")
      (node (ref "R247") (pin "1") (pinfunction "1_1") (pintype "passive"))
    )
    (net (code "34") (name "SIN") (class "Default")
      (node (ref "C19") (pin "1") (pinfunction "1_1") (pintype "passive"))
      (node (ref "R60") (pin "2") (pinfunction "2_2") (pintype "passive"))
    )
    (net (code "35") (name "unconnected-(U39-NC-Pad7)") (class "Default")
      (node (ref "U39") (pin "7") (pinfunction "NC_7") (pintype "passive"))
    )
    (net (code "36") (name "unconnected-(U39-NC-Pad8)") (class "Default")
      (node (ref "U39") (pin "8") (pinfunction "NC_8") (pintype "passive"))
    )
  )
)
